# espboard.net
KiCad netlist of a schematic drawn in EAGLE
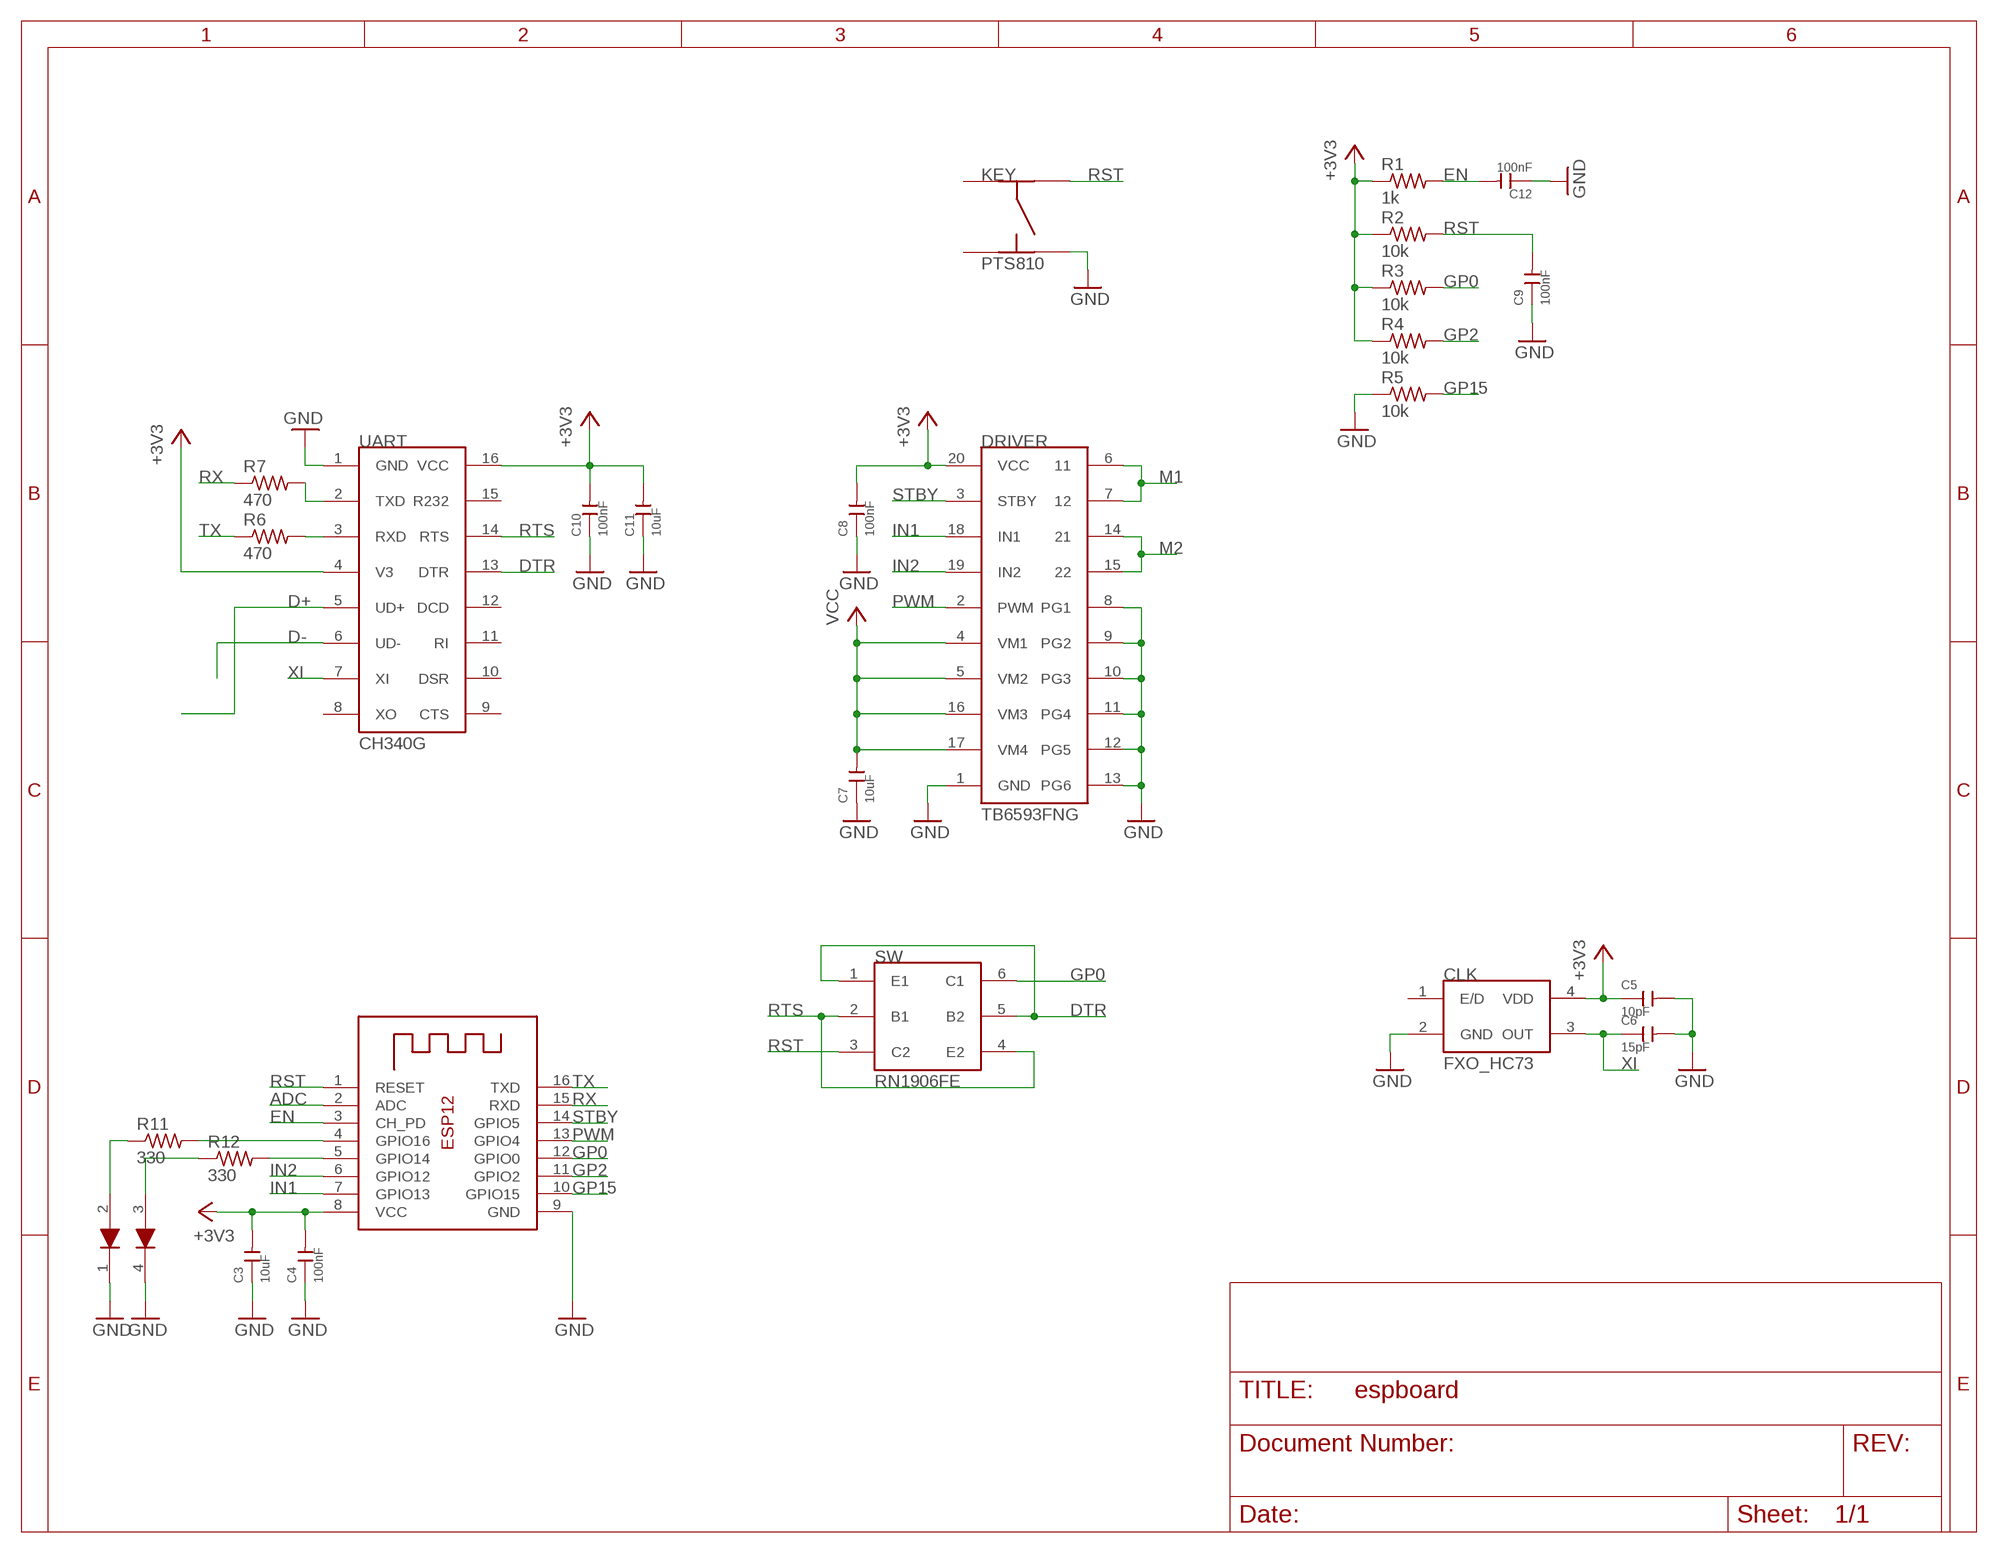
[diagram p0: schematic, sheet 1]

(export (version "E")
  (design (tool "Eeschema 10.0.6"))
  (components
    (comp (ref "C3")
      (value "10uF")
      (footprint "eagle-import:C0603")
      (libsource (lib "eagle-import") (part "CERAMIC-0.5PF-50V-0.1PF-NPO(0603)"))
    )
    (comp (ref "C4")
      (value "100nF")
      (footprint "eagle-import:C0603")
      (libsource (lib "eagle-import") (part "CERAMIC-0.5PF-50V-0.1PF-NPO(0603)"))
    )
    (comp (ref "C5")
      (value "10pF")
      (footprint "eagle-import:C0603")
      (libsource (lib "eagle-import") (part "CERAMIC-0.5PF-50V-0.1PF-NPO(0603)"))
    )
    (comp (ref "C6")
      (value "15pF")
      (footprint "eagle-import:C0603")
      (libsource (lib "eagle-import") (part "CERAMIC-0.5PF-50V-0.1PF-NPO(0603)"))
    )
    (comp (ref "C7")
      (value "10uF")
      (footprint "eagle-import:C0603")
      (libsource (lib "eagle-import") (part "CERAMIC-0.5PF-50V-0.1PF-NPO(0603)"))
    )
    (comp (ref "C8")
      (value "100nF")
      (footprint "eagle-import:C0603")
      (libsource (lib "eagle-import") (part "CERAMIC-0.5PF-50V-0.1PF-NPO(0603)"))
    )
    (comp (ref "C9")
      (value "100nF")
      (footprint "eagle-import:C0603")
      (libsource (lib "eagle-import") (part "CERAMIC-1PF-50V-0.25PF-NPO(0603)"))
    )
    (comp (ref "C10")
      (value "100nF")
      (footprint "eagle-import:C0603")
      (libsource (lib "eagle-import") (part "CERAMIC-0.5PF-50V-0.1PF-NPO(0603)"))
    )
    (comp (ref "C11")
      (value "10uF")
      (footprint "eagle-import:C0603")
      (libsource (lib "eagle-import") (part "CERAMIC-0.5PF-50V-0.1PF-NPO(0603)"))
    )
    (comp (ref "C12")
      (value "100nF")
      (footprint "eagle-import:C0603")
      (libsource (lib "eagle-import") (part "CERAMIC-1PF-50V-0.25PF-NPO(0603)"))
    )
    (comp (ref "CLK")
      (value "FXO_HC73")
      (footprint "eagle-import:4-SMD")
      (libsource (lib "eagle-import") (part "FXO_HC73"))
    )
    (comp (ref "DRIVER")
      (value "TB6593FNG")
      (footprint "eagle-import:SSOP-20")
      (libsource (lib "eagle-import") (part "TB6593FNG"))
    )
    (comp (ref "ESP12")
      (value "ESP-12")
      (footprint "eagle-import:ESP-12")
      (libsource (lib "eagle-import") (part "ESP-12"))
    )
    (comp (ref "KEY")
      (value "PTS810")
      (footprint "eagle-import:BUTTON")
      (libsource (lib "eagle-import") (part "BUTTON"))
    )
    (comp (ref "R1")
      (value "1k")
      (footprint "eagle-import:R0603")
      (libsource (lib "eagle-import") (part "R-US_R0603"))
    )
    (comp (ref "R2")
      (value "10k")
      (footprint "eagle-import:R0603")
      (libsource (lib "eagle-import") (part "R-US_R0603"))
    )
    (comp (ref "R3")
      (value "10k")
      (footprint "eagle-import:R0603")
      (libsource (lib "eagle-import") (part "R-US_R0603"))
    )
    (comp (ref "R4")
      (value "10k")
      (footprint "eagle-import:R0603")
      (libsource (lib "eagle-import") (part "R-US_R0603"))
    )
    (comp (ref "R5")
      (value "10k")
      (footprint "eagle-import:R0603")
      (libsource (lib "eagle-import") (part "R-US_R0603"))
    )
    (comp (ref "R6")
      (value "470")
      (footprint "eagle-import:R0603")
      (libsource (lib "eagle-import") (part "R-US_R0603"))
    )
    (comp (ref "R7")
      (value "470")
      (footprint "eagle-import:R0603")
      (libsource (lib "eagle-import") (part "R-US_R0603"))
    )
    (comp (ref "R11")
      (value "330")
      (footprint "eagle-import:R0603")
      (libsource (lib "eagle-import") (part "R-US_R0603"))
    )
    (comp (ref "R12")
      (value "330")
      (footprint "eagle-import:R0603")
      (libsource (lib "eagle-import") (part "R-US_R0603"))
    )
    (comp (ref "SW")
      (value "RN1906FE")
      (footprint "eagle-import:SOT-563")
      (libsource (lib "eagle-import") (part "RN1906FE"))
    )
    (comp (ref "U$2")
      (value "BI_LED")
      (footprint "eagle-import:BI_LED")
      (libsource (lib "eagle-import") (part "BI_LED"))
    )
    (comp (ref "UART")
      (value "CH340G")
      (footprint "eagle-import:20-16")
      (libsource (lib "eagle-import") (part "CH340G"))
    )
  )
  (nets
    (net (code "1") (name "+3V3") (class "Default")
      (node (ref "C10") (pin "2") (pinfunction "2_2") (pintype "passive"))
      (node (ref "C11") (pin "2") (pinfunction "2_2") (pintype "passive"))
      (node (ref "C3") (pin "2") (pinfunction "2_2") (pintype "passive"))
      (node (ref "C4") (pin "2") (pinfunction "2_2") (pintype "passive"))
      (node (ref "C5") (pin "1") (pinfunction "1_1") (pintype "passive"))
      (node (ref "C8") (pin "2") (pinfunction "2_2") (pintype "passive"))
      (node (ref "CLK") (pin "4") (pinfunction "VDD_4") (pintype "bidirectional"))
      (node (ref "DRIVER") (pin "20") (pinfunction "VCC_20") (pintype "bidirectional"))
      (node (ref "ESP12") (pin "8") (pinfunction "VCC_8") (pintype "power_in"))
      (node (ref "R1") (pin "1") (pinfunction "1_1") (pintype "passive"))
      (node (ref "R2") (pin "1") (pinfunction "1_1") (pintype "passive"))
      (node (ref "R3") (pin "1") (pinfunction "1_1") (pintype "passive"))
      (node (ref "R4") (pin "1") (pinfunction "1_1") (pintype "passive"))
      (node (ref "UART") (pin "16") (pinfunction "VCC_16") (pintype "bidirectional"))
      (node (ref "UART") (pin "4") (pinfunction "V3_4") (pintype "bidirectional"))
    )
    (net (code "2") (name "/ADC") (class "Default")
      (node (ref "ESP12") (pin "2") (pinfunction "ADC_2") (pintype "passive"))
    )
    (net (code "3") (name "/D+") (class "Default")
      (node (ref "UART") (pin "5") (pinfunction "UD+_5") (pintype "bidirectional"))
    )
    (net (code "4") (name "/D-") (class "Default")
      (node (ref "UART") (pin "6") (pinfunction "UD-_6") (pintype "bidirectional"))
    )
    (net (code "5") (name "/DTR") (class "Default")
      (node (ref "SW") (pin "1") (pinfunction "E1_1") (pintype "bidirectional"))
      (node (ref "SW") (pin "5") (pinfunction "B2_5") (pintype "bidirectional"))
      (node (ref "UART") (pin "13") (pinfunction "DTR_13") (pintype "bidirectional"))
    )
    (net (code "6") (name "/EN") (class "Default")
      (node (ref "C12") (pin "2") (pinfunction "2_2") (pintype "passive"))
      (node (ref "ESP12") (pin "3") (pinfunction "CH_PD_3") (pintype "input"))
      (node (ref "R1") (pin "2") (pinfunction "2_2") (pintype "passive"))
    )
    (net (code "7") (name "/GP0") (class "Default")
      (node (ref "ESP12") (pin "12") (pinfunction "GPIO0_12") (pintype "bidirectional"))
      (node (ref "R3") (pin "2") (pinfunction "2_2") (pintype "passive"))
      (node (ref "SW") (pin "6") (pinfunction "C1_6") (pintype "bidirectional"))
    )
    (net (code "8") (name "/GP2") (class "Default")
      (node (ref "ESP12") (pin "11") (pinfunction "GPIO2_11") (pintype "bidirectional"))
      (node (ref "R4") (pin "2") (pinfunction "2_2") (pintype "passive"))
    )
    (net (code "9") (name "/GP15") (class "Default")
      (node (ref "ESP12") (pin "10") (pinfunction "GPIO15_10") (pintype "bidirectional"))
      (node (ref "R5") (pin "2") (pinfunction "2_2") (pintype "passive"))
    )
    (net (code "10") (name "/IN1") (class "Default")
      (node (ref "DRIVER") (pin "18") (pinfunction "IN1_18") (pintype "bidirectional"))
      (node (ref "ESP12") (pin "7") (pinfunction "GPIO13_7") (pintype "bidirectional"))
    )
    (net (code "11") (name "/IN2") (class "Default")
      (node (ref "DRIVER") (pin "19") (pinfunction "IN2_19") (pintype "bidirectional"))
      (node (ref "ESP12") (pin "6") (pinfunction "GPIO12_6") (pintype "bidirectional"))
    )
    (net (code "12") (name "/M1") (class "Default")
      (node (ref "DRIVER") (pin "6") (pinfunction "11_6") (pintype "bidirectional"))
      (node (ref "DRIVER") (pin "7") (pinfunction "12_7") (pintype "bidirectional"))
    )
    (net (code "13") (name "/M2") (class "Default")
      (node (ref "DRIVER") (pin "14") (pinfunction "21_14") (pintype "bidirectional"))
      (node (ref "DRIVER") (pin "15") (pinfunction "22_15") (pintype "bidirectional"))
    )
    (net (code "14") (name "/PWM") (class "Default")
      (node (ref "DRIVER") (pin "2") (pinfunction "PWM_2") (pintype "bidirectional"))
      (node (ref "ESP12") (pin "13") (pinfunction "GPIO4_13") (pintype "bidirectional"))
    )
    (net (code "15") (name "/RST") (class "Default")
      (node (ref "C9") (pin "2") (pinfunction "2_2") (pintype "passive"))
      (node (ref "ESP12") (pin "1") (pinfunction "RESET_1") (pintype "input"))
      (node (ref "KEY") (pin "2") (pinfunction "2_2") (pintype "bidirectional"))
      (node (ref "R2") (pin "2") (pinfunction "2_2") (pintype "passive"))
      (node (ref "SW") (pin "3") (pinfunction "C2_3") (pintype "bidirectional"))
    )
    (net (code "16") (name "/RTS") (class "Default")
      (node (ref "SW") (pin "2") (pinfunction "B1_2") (pintype "bidirectional"))
      (node (ref "SW") (pin "4") (pinfunction "E2_4") (pintype "bidirectional"))
      (node (ref "UART") (pin "14") (pinfunction "RTS_14") (pintype "bidirectional"))
    )
    (net (code "17") (name "/RX") (class "Default")
      (node (ref "ESP12") (pin "15") (pinfunction "RXD_15") (pintype "input"))
      (node (ref "R7") (pin "1") (pinfunction "1_1") (pintype "passive"))
    )
    (net (code "18") (name "/STBY") (class "Default")
      (node (ref "DRIVER") (pin "3") (pinfunction "STBY_3") (pintype "bidirectional"))
      (node (ref "ESP12") (pin "14") (pinfunction "GPIO5_14") (pintype "bidirectional"))
    )
    (net (code "19") (name "/TX") (class "Default")
      (node (ref "ESP12") (pin "16") (pinfunction "TXD_16") (pintype "output"))
      (node (ref "R6") (pin "1") (pinfunction "1_1") (pintype "passive"))
    )
    (net (code "20") (name "/XI") (class "Default")
      (node (ref "C6") (pin "1") (pinfunction "1_1") (pintype "passive"))
      (node (ref "CLK") (pin "3") (pinfunction "OUT_3") (pintype "bidirectional"))
      (node (ref "UART") (pin "7") (pinfunction "XI_7") (pintype "bidirectional"))
    )
    (net (code "21") (name "GND") (class "Default")
      (node (ref "C10") (pin "1") (pinfunction "1_1") (pintype "passive"))
      (node (ref "C11") (pin "1") (pinfunction "1_1") (pintype "passive"))
      (node (ref "C12") (pin "1") (pinfunction "1_1") (pintype "passive"))
      (node (ref "C3") (pin "1") (pinfunction "1_1") (pintype "passive"))
      (node (ref "C4") (pin "1") (pinfunction "1_1") (pintype "passive"))
      (node (ref "C5") (pin "2") (pinfunction "2_2") (pintype "passive"))
      (node (ref "C6") (pin "2") (pinfunction "2_2") (pintype "passive"))
      (node (ref "C7") (pin "1") (pinfunction "1_1") (pintype "passive"))
      (node (ref "C8") (pin "1") (pinfunction "1_1") (pintype "passive"))
      (node (ref "C9") (pin "1") (pinfunction "1_1") (pintype "passive"))
      (node (ref "CLK") (pin "2") (pinfunction "GND_2") (pintype "bidirectional"))
      (node (ref "DRIVER") (pin "1") (pinfunction "GND_1") (pintype "bidirectional"))
      (node (ref "DRIVER") (pin "10") (pinfunction "PG3_10") (pintype "bidirectional"))
      (node (ref "DRIVER") (pin "11") (pinfunction "PG4_11") (pintype "bidirectional"))
      (node (ref "DRIVER") (pin "12") (pinfunction "PG5_12") (pintype "bidirectional"))
      (node (ref "DRIVER") (pin "13") (pinfunction "PG6_13") (pintype "bidirectional"))
      (node (ref "DRIVER") (pin "8") (pinfunction "PG1_8") (pintype "bidirectional"))
      (node (ref "DRIVER") (pin "9") (pinfunction "PG2_9") (pintype "bidirectional"))
      (node (ref "ESP12") (pin "9") (pinfunction "GND_9") (pintype "power_in"))
      (node (ref "KEY") (pin "4") (pinfunction "4_4") (pintype "bidirectional"))
      (node (ref "R5") (pin "1") (pinfunction "1_1") (pintype "passive"))
      (node (ref "U$2") (pin "1") (pinfunction "1_1") (pintype "bidirectional"))
      (node (ref "U$2") (pin "4") (pinfunction "4_4") (pintype "bidirectional"))
      (node (ref "UART") (pin "1") (pinfunction "GND_1") (pintype "bidirectional"))
    )
    (net (code "22") (name "Net-(ESP12-GPIO14)") (class "Default")
      (node (ref "ESP12") (pin "5") (pinfunction "GPIO14_5") (pintype "bidirectional"))
      (node (ref "R12") (pin "2") (pinfunction "2_2") (pintype "passive"))
    )
    (net (code "23") (name "Net-(ESP12-GPIO16)") (class "Default")
      (node (ref "ESP12") (pin "4") (pinfunction "GPIO16_4") (pintype "bidirectional"))
      (node (ref "R11") (pin "2") (pinfunction "2_2") (pintype "passive"))
    )
    (net (code "24") (name "Net-(R11-Pad1)") (class "Default")
      (node (ref "R11") (pin "1") (pinfunction "1_1") (pintype "passive"))
      (node (ref "U$2") (pin "2") (pinfunction "2_2") (pintype "bidirectional"))
    )
    (net (code "25") (name "Net-(R12-Pad1)") (class "Default")
      (node (ref "R12") (pin "1") (pinfunction "1_1") (pintype "passive"))
      (node (ref "U$2") (pin "3") (pinfunction "3_3") (pintype "bidirectional"))
    )
    (net (code "26") (name "Net-(UART-RXD)") (class "Default")
      (node (ref "R6") (pin "2") (pinfunction "2_2") (pintype "passive"))
      (node (ref "UART") (pin "3") (pinfunction "RXD_3") (pintype "bidirectional"))
    )
    (net (code "27") (name "Net-(UART-TXD)") (class "Default")
      (node (ref "R7") (pin "2") (pinfunction "2_2") (pintype "passive"))
      (node (ref "UART") (pin "2") (pinfunction "TXD_2") (pintype "bidirectional"))
    )
    (net (code "28") (name "VCC") (class "Default")
      (node (ref "C7") (pin "2") (pinfunction "2_2") (pintype "passive"))
      (node (ref "DRIVER") (pin "16") (pinfunction "VM3_16") (pintype "bidirectional"))
      (node (ref "DRIVER") (pin "17") (pinfunction "VM4_17") (pintype "bidirectional"))
      (node (ref "DRIVER") (pin "4") (pinfunction "VM1_4") (pintype "bidirectional"))
      (node (ref "DRIVER") (pin "5") (pinfunction "VM2_5") (pintype "bidirectional"))
    )
    (net (code "29") (name "unconnected-(CLK-E{slash}D-Pad1)") (class "Default")
      (node (ref "CLK") (pin "1") (pinfunction "E/D_1") (pintype "bidirectional"))
    )
    (net (code "30") (name "unconnected-(KEY-Pad1)") (class "Default")
      (node (ref "KEY") (pin "1") (pinfunction "1_1") (pintype "bidirectional"))
    )
    (net (code "31") (name "unconnected-(KEY-Pad3)") (class "Default")
      (node (ref "KEY") (pin "3") (pinfunction "3_3") (pintype "bidirectional"))
    )
    (net (code "32") (name "unconnected-(UART-CTS-Pad9)") (class "Default")
      (node (ref "UART") (pin "9") (pinfunction "CTS_9") (pintype "bidirectional"))
    )
    (net (code "33") (name "unconnected-(UART-DCD-Pad12)") (class "Default")
      (node (ref "UART") (pin "12") (pinfunction "DCD_12") (pintype "bidirectional"))
    )
    (net (code "34") (name "unconnected-(UART-DSR-Pad10)") (class "Default")
      (node (ref "UART") (pin "10") (pinfunction "DSR_10") (pintype "bidirectional"))
    )
    (net (code "35") (name "unconnected-(UART-R232-Pad15)") (class "Default")
      (node (ref "UART") (pin "15") (pinfunction "R232_15") (pintype "bidirectional"))
    )
    (net (code "36") (name "unconnected-(UART-RI-Pad11)") (class "Default")
      (node (ref "UART") (pin "11") (pinfunction "RI_11") (pintype "bidirectional"))
    )
    (net (code "37") (name "unconnected-(UART-XO-Pad8)") (class "Default")
      (node (ref "UART") (pin "8") (pinfunction "XO_8") (pintype "bidirectional"))
    )
  )
)
